# NCP1402_5V_step-up-v10.net
KiCad netlist of a schematic drawn in EAGLE
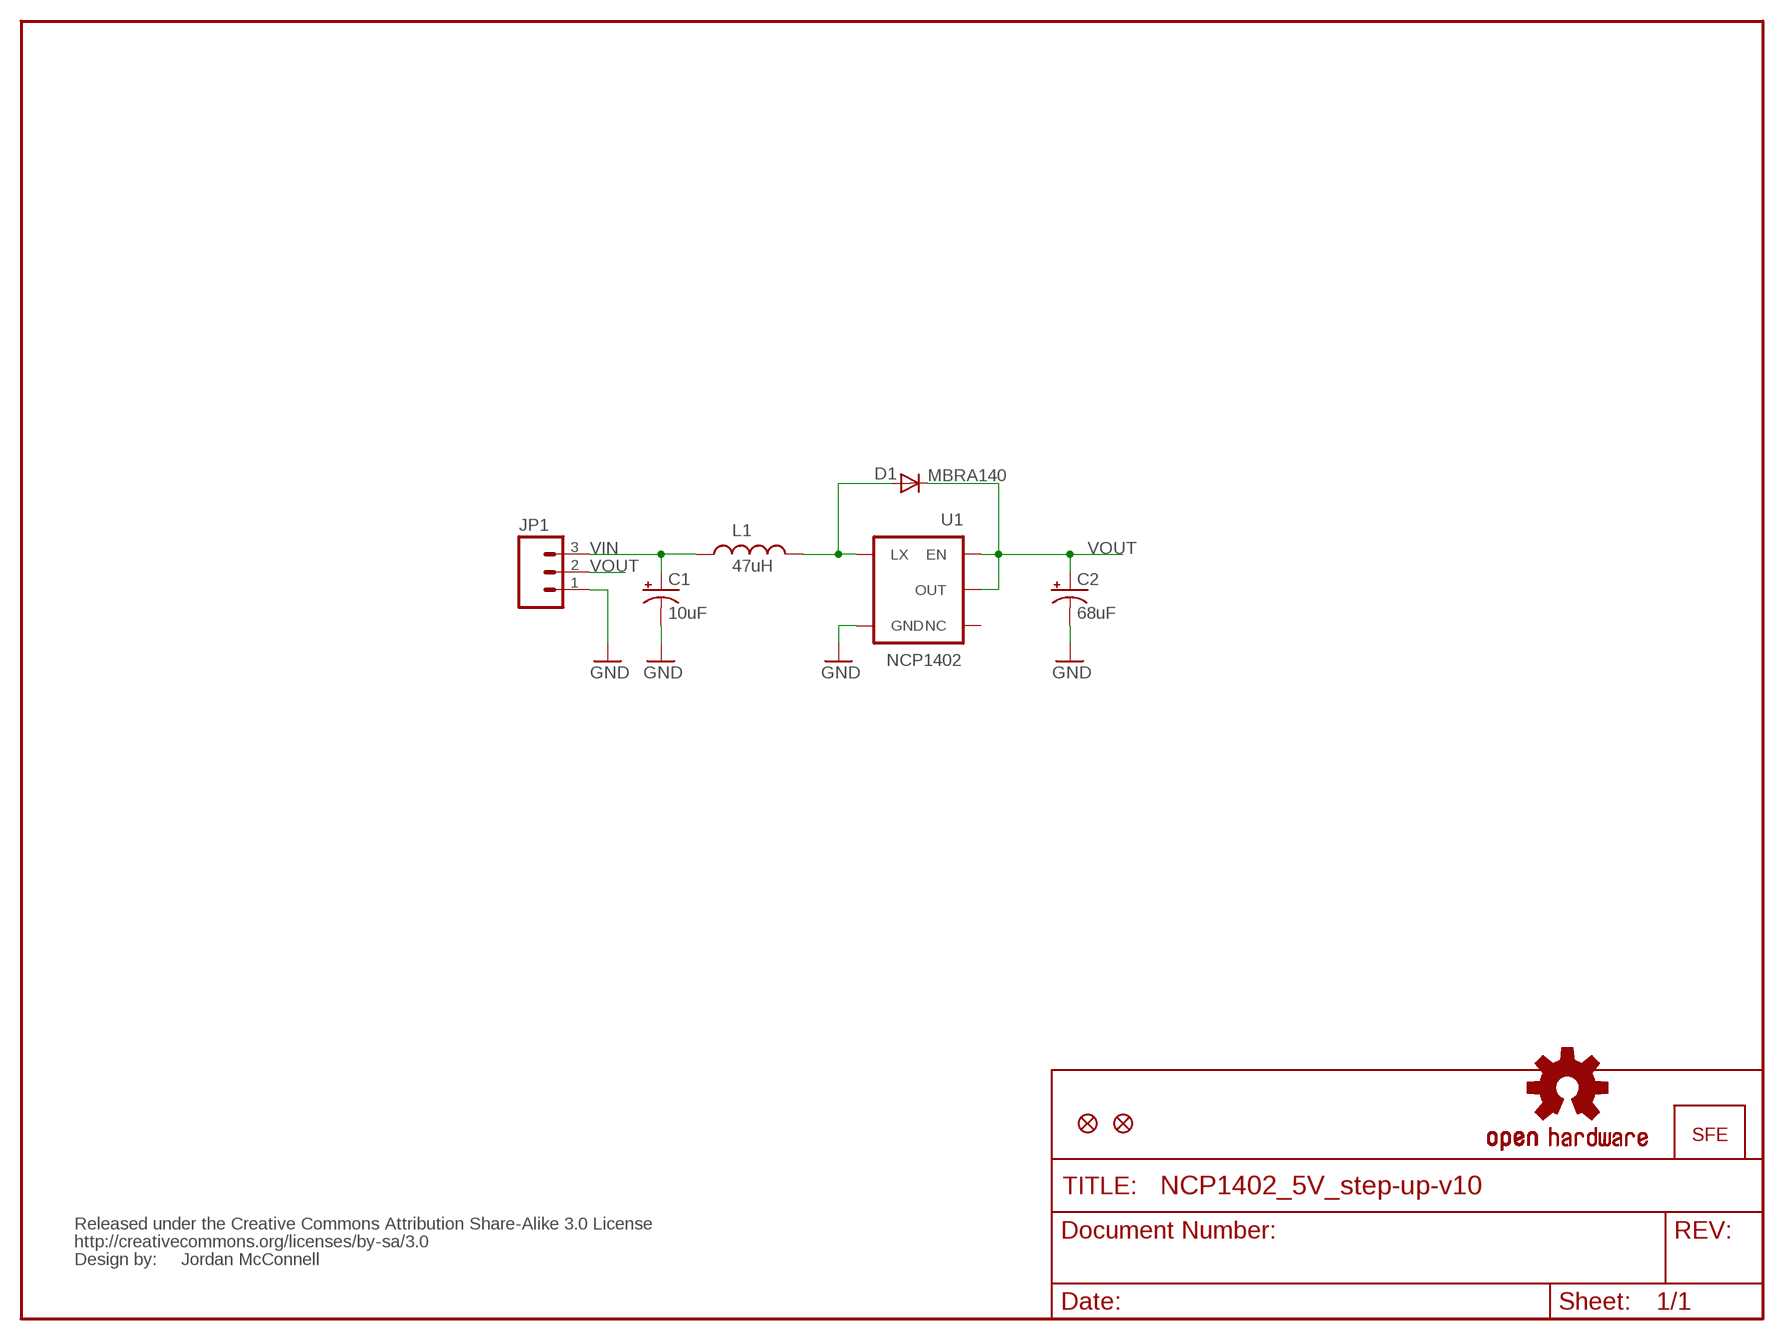
[diagram p0: schematic, sheet 1]

(export (version "E")
  (design (tool "Eeschema 10.0.6"))
  (components
    (comp (ref "C1")
      (value "10uF")
      (footprint "eagle-import:EIA3216")
      (libsource (lib "eagle-import") (part "CAP_POL1206"))
    )
    (comp (ref "C2")
      (value "68uF")
      (footprint "eagle-import:EIA3528")
      (libsource (lib "eagle-import") (part "CAP_POL3528"))
    )
    (comp (ref "D1")
      (value "MBRA140")
      (footprint "eagle-import:SMA-DIODE")
      (libsource (lib "eagle-import") (part "DIODESMA"))
    )
    (comp (ref "JP1")
      (value "M03PTH")
      (footprint "eagle-import:1X03")
      (libsource (lib "eagle-import") (part "M03PTH"))
    )
    (comp (ref "JP2")
      (value "LOGO-SFESK")
      (footprint "eagle-import:SFE-LOGO-FLAME")
      (libsource (lib "eagle-import") (part "LOGO-SFESK"))
    )
    (comp (ref "JP3")
      (value "FIDUCIALUFIDUCIAL")
      (footprint "eagle-import:MICRO-FIDUCIAL")
      (libsource (lib "eagle-import") (part "FIDUCIALUFIDUCIAL"))
    )
    (comp (ref "JP4")
      (value "FIDUCIALUFIDUCIAL")
      (footprint "eagle-import:MICRO-FIDUCIAL")
      (libsource (lib "eagle-import") (part "FIDUCIALUFIDUCIAL"))
    )
    (comp (ref "L1")
      (value "47uH")
      (footprint "eagle-import:CR54")
      (libsource (lib "eagle-import") (part "INDUCTORCR54"))
    )
    (comp (ref "U$1")
      (value "OSHW-LOGOS")
      (footprint "eagle-import:OSHW-LOGO-S")
      (libsource (lib "eagle-import") (part "OSHW-LOGOS"))
    )
    (comp (ref "U$2")
      (value "CREATIVE_COMMONS")
      (footprint "eagle-import:CREATIVE_COMMONS")
      (libsource (lib "eagle-import") (part "CREATIVE_COMMONS"))
    )
    (comp (ref "U1")
      (value "NCP1402")
      (footprint "eagle-import:SOT23-5")
      (libsource (lib "eagle-import") (part "V_REG_NCP1400SOT23-5"))
    )
  )
  (nets
    (net (code "1") (name "/VIN") (class "Default")
      (node (ref "C1") (pin "A") (pinfunction "+_A") (pintype "passive"))
      (node (ref "JP1") (pin "3") (pinfunction "3_3") (pintype "passive"))
      (node (ref "L1") (pin "P$1") (pinfunction "1_P$1") (pintype "passive"))
    )
    (net (code "2") (name "/VOUT") (class "Default")
      (node (ref "C2") (pin "A") (pinfunction "+_A") (pintype "passive"))
      (node (ref "D1") (pin "C") (pinfunction "C_C") (pintype "passive"))
      (node (ref "JP1") (pin "2") (pinfunction "2_2") (pintype "passive"))
      (node (ref "U1") (pin "1") (pinfunction "EN_1") (pintype "input"))
      (node (ref "U1") (pin "2") (pinfunction "OUT_2") (pintype "passive"))
    )
    (net (code "3") (name "GND") (class "Default")
      (node (ref "C1") (pin "C") (pinfunction "-_C") (pintype "passive"))
      (node (ref "C2") (pin "C") (pinfunction "-_C") (pintype "passive"))
      (node (ref "JP1") (pin "1") (pinfunction "1_1") (pintype "passive"))
      (node (ref "U1") (pin "4") (pinfunction "GND_4") (pintype "input"))
    )
    (net (code "4") (name "Net-(L1-2)") (class "Default")
      (node (ref "D1") (pin "A") (pinfunction "A_A") (pintype "passive"))
      (node (ref "L1") (pin "P$2") (pinfunction "2_P$2") (pintype "passive"))
      (node (ref "U1") (pin "5") (pinfunction "LX_5") (pintype "input"))
    )
    (net (code "5") (name "unconnected-(U1-NC-Pad3)") (class "Default")
      (node (ref "U1") (pin "3") (pinfunction "NC_3") (pintype "input"))
    )
  )
)
